# hand-unit.net
KiCad netlist of a schematic drawn in EAGLE
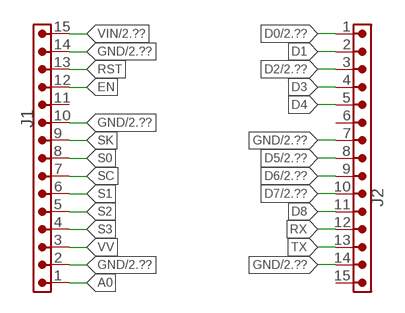
[diagram p0: schematic, sheet 1]
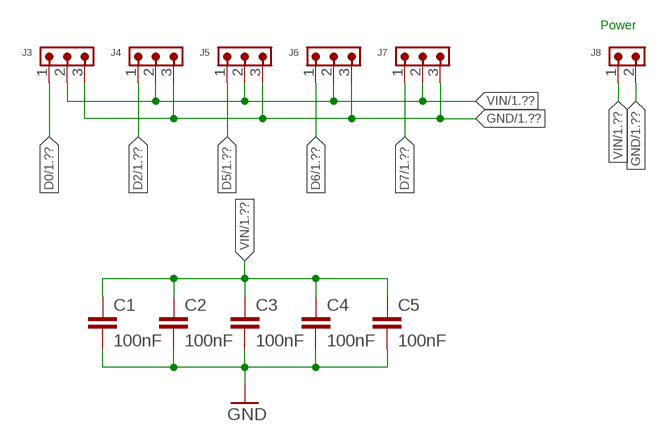
[diagram p1: schematic, sheet 2]

(export (version "E")
  (design (tool "Eeschema 10.0.6"))
  (components
    (comp (ref "C1")
      (value "100nF")
      (footprint "eagle-import:C0603")
      (libsource (lib "eagle-import") (part "CC0603"))
    )
    (comp (ref "C2")
      (value "100nF")
      (footprint "eagle-import:C0603")
      (libsource (lib "eagle-import") (part "CC0603"))
    )
    (comp (ref "C3")
      (value "100nF")
      (footprint "eagle-import:C0603")
      (libsource (lib "eagle-import") (part "CC0603"))
    )
    (comp (ref "C4")
      (value "100nF")
      (footprint "eagle-import:C0603")
      (libsource (lib "eagle-import") (part "CC0603"))
    )
    (comp (ref "C5")
      (value "100nF")
      (footprint "eagle-import:C0603")
      (libsource (lib "eagle-import") (part "CC0603"))
    )
    (comp (ref "J3")
      (value "6130XX11121_61300311121")
      (footprint "eagle-import:61300311121")
      (libsource (lib "eagle-import") (part "6130XX11121_61300311121"))
    )
    (comp (ref "J4")
      (value "6130XX11121_61300311121")
      (footprint "eagle-import:61300311121")
      (libsource (lib "eagle-import") (part "6130XX11121_61300311121"))
    )
    (comp (ref "J5")
      (value "6130XX11121_61300311121")
      (footprint "eagle-import:61300311121")
      (libsource (lib "eagle-import") (part "6130XX11121_61300311121"))
    )
    (comp (ref "J6")
      (value "6130XX11121_61300311121")
      (footprint "eagle-import:61300311121")
      (libsource (lib "eagle-import") (part "6130XX11121_61300311121"))
    )
    (comp (ref "J7")
      (value "6130XX11121_61300311121")
      (footprint "eagle-import:61300311121")
      (libsource (lib "eagle-import") (part "6130XX11121_61300311121"))
    )
    (comp (ref "J8")
      (value "6130XX11121_61300211121")
      (footprint "eagle-import:61300211121")
      (libsource (lib "eagle-import") (part "6130XX11121_61300211121"))
    )
    (comp (ref "J1")
      (value "6130XX11121_61301511121")
      (footprint "eagle-import:61301511121")
      (libsource (lib "eagle-import") (part "6130XX11121_61301511121"))
    )
    (comp (ref "J2")
      (value "6130XX11121_61301511121")
      (footprint "eagle-import:61301511121")
      (libsource (lib "eagle-import") (part "6130XX11121_61301511121"))
    )
  )
  (nets
    (net (code "1") (name "A0") (class "Default")
      (node (ref "J1") (pin "1") (pinfunction "1_1") (pintype "passive"))
    )
    (net (code "2") (name "D0") (class "Default")
      (node (ref "J2") (pin "1") (pinfunction "1_1") (pintype "passive"))
      (node (ref "J3") (pin "1") (pinfunction "1_1") (pintype "passive"))
    )
    (net (code "3") (name "D1") (class "Default")
      (node (ref "J2") (pin "2") (pinfunction "2_2") (pintype "passive"))
    )
    (net (code "4") (name "D2") (class "Default")
      (node (ref "J2") (pin "3") (pinfunction "3_3") (pintype "passive"))
      (node (ref "J4") (pin "1") (pinfunction "1_1") (pintype "passive"))
    )
    (net (code "5") (name "D3") (class "Default")
      (node (ref "J2") (pin "4") (pinfunction "4_4") (pintype "passive"))
    )
    (net (code "6") (name "D4") (class "Default")
      (node (ref "J2") (pin "5") (pinfunction "5_5") (pintype "passive"))
    )
    (net (code "7") (name "D5") (class "Default")
      (node (ref "J2") (pin "8") (pinfunction "8_8") (pintype "passive"))
      (node (ref "J5") (pin "1") (pinfunction "1_1") (pintype "passive"))
    )
    (net (code "8") (name "D6") (class "Default")
      (node (ref "J2") (pin "9") (pinfunction "9_9") (pintype "passive"))
      (node (ref "J6") (pin "1") (pinfunction "1_1") (pintype "passive"))
    )
    (net (code "9") (name "D7") (class "Default")
      (node (ref "J2") (pin "10") (pinfunction "10_10") (pintype "passive"))
      (node (ref "J7") (pin "1") (pinfunction "1_1") (pintype "passive"))
    )
    (net (code "10") (name "D8") (class "Default")
      (node (ref "J2") (pin "11") (pinfunction "11_11") (pintype "passive"))
    )
    (net (code "11") (name "EN") (class "Default")
      (node (ref "J1") (pin "12") (pinfunction "12_12") (pintype "passive"))
    )
    (net (code "12") (name "GND") (class "Default")
      (node (ref "C1") (pin "2") (pinfunction "2_2") (pintype "passive"))
      (node (ref "C2") (pin "2") (pinfunction "2_2") (pintype "passive"))
      (node (ref "C3") (pin "2") (pinfunction "2_2") (pintype "passive"))
      (node (ref "C4") (pin "2") (pinfunction "2_2") (pintype "passive"))
      (node (ref "C5") (pin "2") (pinfunction "2_2") (pintype "passive"))
      (node (ref "J1") (pin "10") (pinfunction "10_10") (pintype "passive"))
      (node (ref "J1") (pin "14") (pinfunction "14_14") (pintype "passive"))
      (node (ref "J1") (pin "2") (pinfunction "2_2") (pintype "passive"))
      (node (ref "J2") (pin "14") (pinfunction "14_14") (pintype "passive"))
      (node (ref "J2") (pin "7") (pinfunction "7_7") (pintype "passive"))
      (node (ref "J3") (pin "3") (pinfunction "3_3") (pintype "passive"))
      (node (ref "J4") (pin "3") (pinfunction "3_3") (pintype "passive"))
      (node (ref "J5") (pin "3") (pinfunction "3_3") (pintype "passive"))
      (node (ref "J6") (pin "3") (pinfunction "3_3") (pintype "passive"))
      (node (ref "J7") (pin "3") (pinfunction "3_3") (pintype "passive"))
      (node (ref "J8") (pin "2") (pinfunction "2_2") (pintype "passive"))
    )
    (net (code "13") (name "RST") (class "Default")
      (node (ref "J1") (pin "13") (pinfunction "13_13") (pintype "passive"))
    )
    (net (code "14") (name "RX") (class "Default")
      (node (ref "J2") (pin "12") (pinfunction "12_12") (pintype "passive"))
    )
    (net (code "15") (name "S0") (class "Default")
      (node (ref "J1") (pin "8") (pinfunction "8_8") (pintype "passive"))
    )
    (net (code "16") (name "S1") (class "Default")
      (node (ref "J1") (pin "6") (pinfunction "6_6") (pintype "passive"))
    )
    (net (code "17") (name "S2") (class "Default")
      (node (ref "J1") (pin "5") (pinfunction "5_5") (pintype "passive"))
    )
    (net (code "18") (name "S3") (class "Default")
      (node (ref "J1") (pin "4") (pinfunction "4_4") (pintype "passive"))
    )
    (net (code "19") (name "SC") (class "Default")
      (node (ref "J1") (pin "7") (pinfunction "7_7") (pintype "passive"))
    )
    (net (code "20") (name "SK") (class "Default")
      (node (ref "J1") (pin "9") (pinfunction "9_9") (pintype "passive"))
    )
    (net (code "21") (name "TX") (class "Default")
      (node (ref "J2") (pin "13") (pinfunction "13_13") (pintype "passive"))
    )
    (net (code "22") (name "VIN") (class "Default")
      (node (ref "C1") (pin "1") (pinfunction "1_1") (pintype "passive"))
      (node (ref "C2") (pin "1") (pinfunction "1_1") (pintype "passive"))
      (node (ref "C3") (pin "1") (pinfunction "1_1") (pintype "passive"))
      (node (ref "C4") (pin "1") (pinfunction "1_1") (pintype "passive"))
      (node (ref "C5") (pin "1") (pinfunction "1_1") (pintype "passive"))
      (node (ref "J1") (pin "15") (pinfunction "15_15") (pintype "passive"))
      (node (ref "J3") (pin "2") (pinfunction "2_2") (pintype "passive"))
      (node (ref "J4") (pin "2") (pinfunction "2_2") (pintype "passive"))
      (node (ref "J5") (pin "2") (pinfunction "2_2") (pintype "passive"))
      (node (ref "J6") (pin "2") (pinfunction "2_2") (pintype "passive"))
      (node (ref "J7") (pin "2") (pinfunction "2_2") (pintype "passive"))
      (node (ref "J8") (pin "1") (pinfunction "1_1") (pintype "passive"))
    )
    (net (code "23") (name "VV") (class "Default")
      (node (ref "J1") (pin "3") (pinfunction "3_3") (pintype "passive"))
    )
    (net (code "24") (name "unconnected-(J1-Pad11)") (class "Default")
      (node (ref "J1") (pin "11") (pinfunction "11_11") (pintype "passive"))
    )
    (net (code "25") (name "unconnected-(J2-Pad6)") (class "Default")
      (node (ref "J2") (pin "6") (pinfunction "6_6") (pintype "passive"))
    )
    (net (code "26") (name "unconnected-(J2-Pad15)") (class "Default")
      (node (ref "J2") (pin "15") (pinfunction "15_15") (pintype "passive"))
    )
  )
)
